# Sensors.net
KiCad netlist of a schematic drawn in Altium Designer
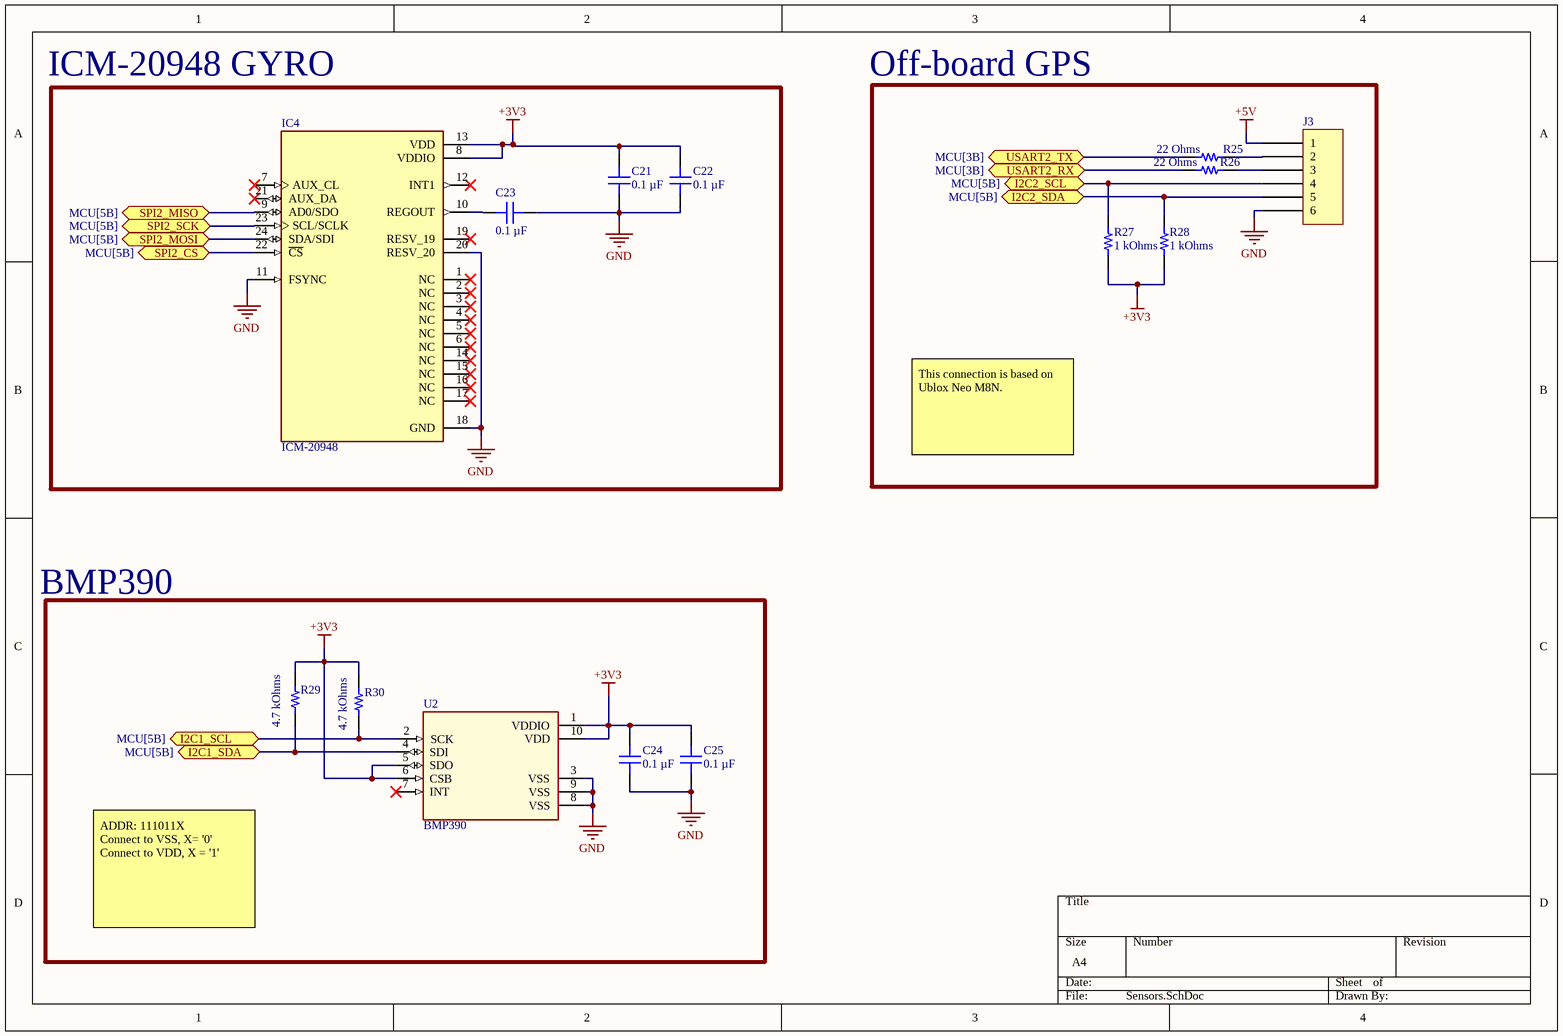
[diagram p0: Sensors.SchDoc]

(export (version "E")
  (design (tool "Eeschema 10.0.6"))
  (components
    (comp (ref "C21")
      (value "0.1 µF")
      (footprint "CAP 0603_1608")
      (description "CAP CER 0.1UF 16V X7R 0603")
      (fields
        (field (name "PART NUMBER") "GCJ188R71C104KA01D")
        (field (name "CAPACITANCE") "0.1 µF")
        (field (name "MANUFACTURER") "Murata Electronics")
      )
      (libsource (lib "Celestial Altium Library - altium_library") (part "Capacitor"))
    )
    (comp (ref "C22")
      (value "0.1 µF")
      (footprint "CAP 0603_1608")
      (description "CAP CER 0.1UF 16V X7R 0603")
      (fields
        (field (name "PART NUMBER") "GCJ188R71C104KA01D")
        (field (name "CAPACITANCE") "0.1 µF")
        (field (name "MANUFACTURER") "Murata Electronics")
      )
      (libsource (lib "Celestial Altium Library - altium_library") (part "Capacitor"))
    )
    (comp (ref "C23")
      (value "0.1 µF")
      (footprint "CAP 0603_1608")
      (description "CAP CER 0.1UF 16V X7R 0603")
      (fields
        (field (name "PART NUMBER") "GCJ188R71C104KA01D")
        (field (name "CAPACITANCE") "0.1 µF")
        (field (name "MANUFACTURER") "Murata Electronics")
      )
      (libsource (lib "Celestial Altium Library - altium_library") (part "Capacitor"))
    )
    (comp (ref "C24")
      (value "0.1 µF")
      (footprint "CAP 0603_1608")
      (description "CAP CER 0.1UF 16V X7R 0603")
      (fields
        (field (name "PART NUMBER") "GCJ188R71C104KA01D")
        (field (name "CAPACITANCE") "0.1 µF")
        (field (name "MANUFACTURER") "Murata Electronics")
      )
      (libsource (lib "Celestial Altium Library - altium_library") (part "Capacitor"))
    )
    (comp (ref "C25")
      (value "0.1 µF")
      (footprint "CAP 0603_1608")
      (description "CAP CER 0.1UF 16V X7R 0603")
      (fields
        (field (name "PART NUMBER") "GCJ188R71C104KA01D")
        (field (name "CAPACITANCE") "0.1 µF")
        (field (name "MANUFACTURER") "Murata Electronics")
      )
      (libsource (lib "Celestial Altium Library - altium_library") (part "Capacitor"))
    )
    (comp (ref "IC4")
      (value "ICM-20948")
      (footprint "ICM-20948")
      (description "Accelerometer, Gyroscope, Magnetometer, 9 Axis Sensor I2C, SPI Output")
      (libsource (lib "PCB_Lib") (part "ICM-20948"))
    )
    (comp (ref "J3")
      (value "SM06B-SRSS-TB(LF)(SN)")
      (footprint "JST SM06B-SRSS-TB")
      (description "CONN HEADER SMD R/A 6POS 1MM")
      (fields (field (name "MANUFACTURER") "JST Sales America Inc."))
      (libsource (lib "Celestial Altium Library - altium_library") (part "6 Pin"))
    )
    (comp (ref "R25")
      (value "22 Ohms")
      (footprint "YAGEO RES 0402_1005")
      (description "RES SMD 22 OHM 5% 1/16W 0402")
      (fields (field (name "PART NUMBER") "AC0402JR-0722RL") (field (name "MANUFACTURER") "Yageo"))
      (libsource (lib "Celestial Altium Library - altium_library") (part "Resistor"))
    )
    (comp (ref "R26")
      (value "22 Ohms")
      (footprint "YAGEO RES 0402_1005")
      (description "RES SMD 22 OHM 5% 1/16W 0402")
      (fields (field (name "PART NUMBER") "AC0402JR-0722RL") (field (name "MANUFACTURER") "Yageo"))
      (libsource (lib "Celestial Altium Library - altium_library") (part "Resistor"))
    )
    (comp (ref "R27")
      (value "1 kOhms")
      (footprint "YAGEO RES 0402_1005")
      (description "RES SMD 1K OHM 5% 1/16W 0402")
      (fields (field (name "PART NUMBER") "AC0402JR-071KL") (field (name "MANUFACTURER") "Yageo"))
      (libsource (lib "Celestial Altium Library - altium_library") (part "Resistor"))
    )
    (comp (ref "R28")
      (value "1 kOhms")
      (footprint "YAGEO RES 0402_1005")
      (description "RES SMD 1K OHM 5% 1/16W 0402")
      (fields (field (name "PART NUMBER") "AC0402JR-071KL") (field (name "MANUFACTURER") "Yageo"))
      (libsource (lib "Celestial Altium Library - altium_library") (part "Resistor"))
    )
    (comp (ref "R29")
      (value "4.7 kOhms")
      (footprint "YAGEO RES 0402_1005")
      (description "RES SMD 4.7K OHM 1% 1/16W 0402")
      (fields (field (name "PART NUMBER") "RT0402FRE074K7L") (field (name "MANUFACTURER") "Yageo"))
      (libsource (lib "Celestial Altium Library - altium_library") (part "Resistor"))
    )
    (comp (ref "R30")
      (value "4.7 kOhms")
      (footprint "YAGEO RES 0402_1005")
      (description "RES SMD 4.7K OHM 1% 1/16W 0402")
      (fields (field (name "PART NUMBER") "RT0402FRE074K7L") (field (name "MANUFACTURER") "Yageo"))
      (libsource (lib "Celestial Altium Library - altium_library") (part "Resistor"))
    )
    (comp (ref "U2")
      (value "BMP390")
      (footprint "BMP390")
      (description "Pressure Sensor 4.35PSI ~ 18.13PSI (30kPa ~ 125kPa) Absolute 10-WFLGA")
      (fields (field (name "MANUFACTURER") "Bosch Sensortech"))
      (libsource (lib "PCB_Lib") (part "BMP390"))
    )
  )
  (nets
    (net (code "1") (name "+3V3") (class "Default")
      (node (ref "C21") (pin "2") (pinfunction "2_2") (pintype "passive"))
      (node (ref "C22") (pin "2") (pinfunction "2_2") (pintype "passive"))
      (node (ref "C24") (pin "2") (pinfunction "2_2") (pintype "passive"))
      (node (ref "C25") (pin "2") (pinfunction "2_2") (pintype "passive"))
      (node (ref "IC4") (pin "13") (pinfunction "VDD_13") (pintype "power_in"))
      (node (ref "IC4") (pin "8") (pinfunction "VDDIO_8") (pintype "power_in"))
      (node (ref "R27") (pin "1") (pinfunction "1_1") (pintype "passive"))
      (node (ref "R28") (pin "1") (pinfunction "1_1") (pintype "passive"))
      (node (ref "R29") (pin "2") (pinfunction "2_2") (pintype "passive"))
      (node (ref "R30") (pin "2") (pinfunction "2_2") (pintype "passive"))
      (node (ref "U2") (pin "1") (pinfunction "VDDIO_1") (pintype "power_in"))
      (node (ref "U2") (pin "10") (pinfunction "VDD_10") (pintype "power_in"))
      (node (ref "U2") (pin "5") (pinfunction "SDO_5") (pintype "bidirectional"))
      (node (ref "U2") (pin "6") (pinfunction "CSB_6") (pintype "input"))
    )
    (net (code "2") (name "+5V") (class "Default")
      (node (ref "J3") (pin "1") (pinfunction "1_1") (pintype "passive"))
    )
    (net (code "3") (name "/I2C1_SCL") (class "Default")
      (node (ref "R30") (pin "1") (pinfunction "1_1") (pintype "passive"))
      (node (ref "U2") (pin "2") (pinfunction "SCK_2") (pintype "input"))
    )
    (net (code "4") (name "/I2C1_SDA") (class "Default")
      (node (ref "R29") (pin "1") (pinfunction "1_1") (pintype "passive"))
      (node (ref "U2") (pin "4") (pinfunction "SDI_4") (pintype "bidirectional"))
    )
    (net (code "5") (name "/I2C2_SCL") (class "Default")
      (node (ref "J3") (pin "4") (pinfunction "4_4") (pintype "passive"))
      (node (ref "R27") (pin "2") (pinfunction "2_2") (pintype "passive"))
    )
    (net (code "6") (name "/I2C2_SDA") (class "Default")
      (node (ref "J3") (pin "5") (pinfunction "5_5") (pintype "passive"))
      (node (ref "R28") (pin "2") (pinfunction "2_2") (pintype "passive"))
    )
    (net (code "7") (name "/SPI2_CS") (class "Default")
      (node (ref "IC4") (pin "22") (pinfunction "~{CS}_22") (pintype "input"))
    )
    (net (code "8") (name "/SPI2_MISO") (class "Default")
      (node (ref "IC4") (pin "9") (pinfunction "AD0/SDO_9") (pintype "bidirectional"))
    )
    (net (code "9") (name "/SPI2_MOSI") (class "Default")
      (node (ref "IC4") (pin "24") (pinfunction "SDA/SDI_24") (pintype "bidirectional"))
    )
    (net (code "10") (name "/SPI2_SCK") (class "Default")
      (node (ref "IC4") (pin "23") (pinfunction "SCL/SCLK_23") (pintype "input"))
    )
    (net (code "11") (name "/USART2_RX") (class "Default")
      (node (ref "R26") (pin "1") (pinfunction "1_1") (pintype "passive"))
    )
    (net (code "12") (name "/USART2_TX") (class "Default")
      (node (ref "R25") (pin "1") (pinfunction "1_1") (pintype "passive"))
    )
    (net (code "13") (name "GND") (class "Default")
      (node (ref "C21") (pin "1") (pinfunction "1_1") (pintype "passive"))
      (node (ref "C22") (pin "1") (pinfunction "1_1") (pintype "passive"))
      (node (ref "C23") (pin "1") (pinfunction "1_1") (pintype "passive"))
      (node (ref "C24") (pin "1") (pinfunction "1_1") (pintype "passive"))
      (node (ref "C25") (pin "1") (pinfunction "1_1") (pintype "passive"))
      (node (ref "IC4") (pin "11") (pinfunction "FSYNC_11") (pintype "input"))
      (node (ref "IC4") (pin "18") (pinfunction "GND_18") (pintype "power_in"))
      (node (ref "IC4") (pin "20") (pinfunction "RESV_20_20") (pintype "passive"))
      (node (ref "J3") (pin "6") (pinfunction "6_6") (pintype "passive"))
      (node (ref "U2") (pin "3") (pinfunction "VSS_3") (pintype "power_in"))
      (node (ref "U2") (pin "8") (pinfunction "VSS_8") (pintype "power_in"))
      (node (ref "U2") (pin "9") (pinfunction "VSS_9") (pintype "power_in"))
    )
    (net (code "14") (name "Net-(IC4-REGOUT)") (class "Default")
      (node (ref "C23") (pin "2") (pinfunction "2_2") (pintype "passive"))
      (node (ref "IC4") (pin "10") (pinfunction "REGOUT_10") (pintype "output"))
    )
    (net (code "15") (name "Net-(J3-Pad2)") (class "Default")
      (node (ref "J3") (pin "2") (pinfunction "2_2") (pintype "passive"))
      (node (ref "R25") (pin "2") (pinfunction "2_2") (pintype "passive"))
    )
    (net (code "16") (name "Net-(J3-Pad3)") (class "Default")
      (node (ref "J3") (pin "3") (pinfunction "3_3") (pintype "passive"))
      (node (ref "R26") (pin "2") (pinfunction "2_2") (pintype "passive"))
    )
    (net (code "17") (name "unconnected-(IC4-AUX_CL-Pad7)") (class "Default")
      (node (ref "IC4") (pin "7") (pinfunction "AUX_CL_7") (pintype "input+no_connect"))
    )
    (net (code "18") (name "unconnected-(IC4-AUX_DA-Pad21)") (class "Default")
      (node (ref "IC4") (pin "21") (pinfunction "AUX_DA_21") (pintype "bidirectional+no_connect"))
    )
    (net (code "19") (name "unconnected-(IC4-INT1-Pad12)") (class "Default")
      (node (ref "IC4") (pin "12") (pinfunction "INT1_12") (pintype "output+no_connect"))
    )
    (net (code "20") (name "unconnected-(IC4-NC-Pad1)") (class "Default")
      (node (ref "IC4") (pin "1") (pinfunction "NC_1") (pintype "passive+no_connect"))
    )
    (net (code "21") (name "unconnected-(IC4-NC-Pad2)") (class "Default")
      (node (ref "IC4") (pin "2") (pinfunction "NC_2") (pintype "passive+no_connect"))
    )
    (net (code "22") (name "unconnected-(IC4-NC-Pad3)") (class "Default")
      (node (ref "IC4") (pin "3") (pinfunction "NC_3") (pintype "passive+no_connect"))
    )
    (net (code "23") (name "unconnected-(IC4-NC-Pad4)") (class "Default")
      (node (ref "IC4") (pin "4") (pinfunction "NC_4") (pintype "passive+no_connect"))
    )
    (net (code "24") (name "unconnected-(IC4-NC-Pad5)") (class "Default")
      (node (ref "IC4") (pin "5") (pinfunction "NC_5") (pintype "passive+no_connect"))
    )
    (net (code "25") (name "unconnected-(IC4-NC-Pad6)") (class "Default")
      (node (ref "IC4") (pin "6") (pinfunction "NC_6") (pintype "passive+no_connect"))
    )
    (net (code "26") (name "unconnected-(IC4-NC-Pad14)") (class "Default")
      (node (ref "IC4") (pin "14") (pinfunction "NC_14") (pintype "passive+no_connect"))
    )
    (net (code "27") (name "unconnected-(IC4-NC-Pad15)") (class "Default")
      (node (ref "IC4") (pin "15") (pinfunction "NC_15") (pintype "passive+no_connect"))
    )
    (net (code "28") (name "unconnected-(IC4-NC-Pad16)") (class "Default")
      (node (ref "IC4") (pin "16") (pinfunction "NC_16") (pintype "passive+no_connect"))
    )
    (net (code "29") (name "unconnected-(IC4-NC-Pad17)") (class "Default")
      (node (ref "IC4") (pin "17") (pinfunction "NC_17") (pintype "passive+no_connect"))
    )
    (net (code "30") (name "unconnected-(IC4-RESV_19-Pad19)") (class "Default")
      (node (ref "IC4") (pin "19") (pinfunction "RESV_19_19") (pintype "passive+no_connect"))
    )
    (net (code "31") (name "unconnected-(U2-INT-Pad7)") (class "Default")
      (node (ref "U2") (pin "7") (pinfunction "INT_7") (pintype "input+no_connect"))
    )
  )
)
